# lab6.net
KiCad netlist of a schematic drawn in EAGLE
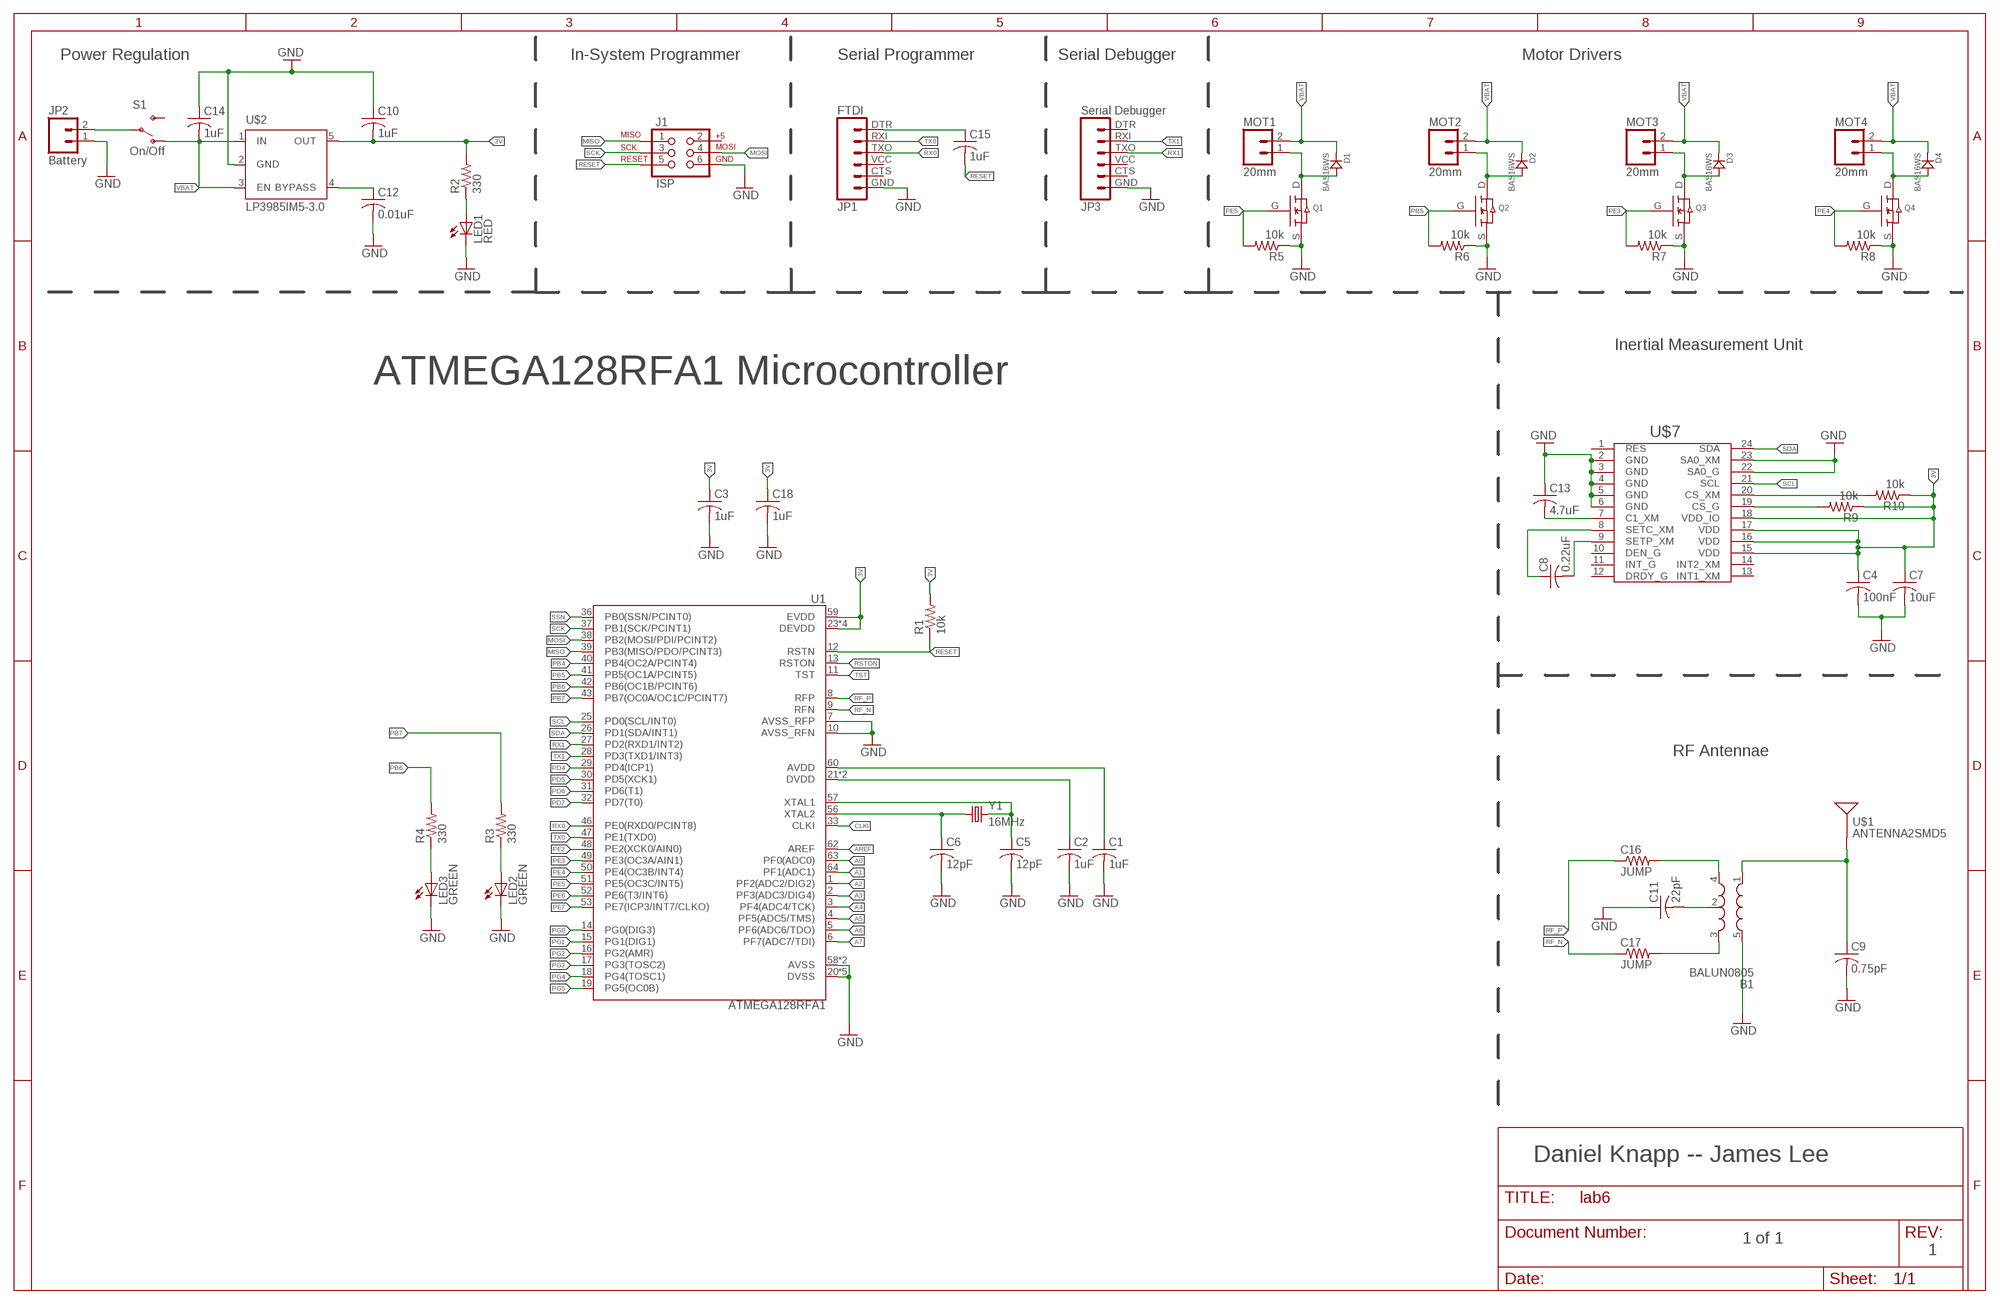
[diagram p0: schematic, sheet 1]

(export (version "E")
  (design (tool "Eeschema 10.0.6"))
  (components
    (comp (ref "B1")
      (value "BALUN0805")
      (footprint "eagle-import:BALUN")
      (libsource (lib "eagle-import") (part "BALUN0805"))
    )
    (comp (ref "C1")
      (value "1uF")
      (footprint "eagle-import:C0805")
      (libsource (lib "eagle-import") (part "C-USC0805"))
    )
    (comp (ref "C2")
      (value "1uF")
      (footprint "eagle-import:C0805")
      (libsource (lib "eagle-import") (part "C-USC0805"))
    )
    (comp (ref "C3")
      (value "1uF")
      (footprint "eagle-import:C0805")
      (libsource (lib "eagle-import") (part "C-USC0805"))
    )
    (comp (ref "C4")
      (value "100nF")
      (footprint "eagle-import:C0805")
      (libsource (lib "eagle-import") (part "C-USC0805"))
    )
    (comp (ref "C5")
      (value "12pF")
      (footprint "eagle-import:C0805")
      (libsource (lib "eagle-import") (part "C-USC0805"))
    )
    (comp (ref "C6")
      (value "12pF")
      (footprint "eagle-import:C0805")
      (libsource (lib "eagle-import") (part "C-USC0805"))
    )
    (comp (ref "C7")
      (value "10uF")
      (footprint "eagle-import:C0805")
      (libsource (lib "eagle-import") (part "C-USC0805"))
    )
    (comp (ref "C8")
      (value "0.22uF")
      (footprint "eagle-import:C0805")
      (libsource (lib "eagle-import") (part "C-USC0805"))
    )
    (comp (ref "C9")
      (value "0.75pF")
      (footprint "eagle-import:C0805")
      (libsource (lib "eagle-import") (part "C-USC0805"))
    )
    (comp (ref "C10")
      (value "1uF")
      (footprint "eagle-import:C0805")
      (libsource (lib "eagle-import") (part "C-USC0805"))
    )
    (comp (ref "C11")
      (value "22pF")
      (footprint "eagle-import:C0805")
      (libsource (lib "eagle-import") (part "C-USC0805"))
    )
    (comp (ref "C12")
      (value "0.01uF")
      (footprint "eagle-import:C0805")
      (libsource (lib "eagle-import") (part "C-USC0805"))
    )
    (comp (ref "C13")
      (value "4.7uF")
      (footprint "eagle-import:C0805")
      (libsource (lib "eagle-import") (part "C-USC0805"))
    )
    (comp (ref "C14")
      (value "1uF")
      (footprint "eagle-import:C0805")
      (libsource (lib "eagle-import") (part "C-USC0805"))
    )
    (comp (ref "C15")
      (value "1uF")
      (footprint "eagle-import:C0805")
      (libsource (lib "eagle-import") (part "C-USC0805"))
    )
    (comp (ref "C16")
      (value "JUMP")
      (footprint "eagle-import:R0805")
      (libsource (lib "eagle-import") (part "R-US_R0805"))
    )
    (comp (ref "C17")
      (value "JUMP")
      (footprint "eagle-import:R0805")
      (libsource (lib "eagle-import") (part "R-US_R0805"))
    )
    (comp (ref "C18")
      (value "1uF")
      (footprint "eagle-import:C0805")
      (libsource (lib "eagle-import") (part "C-USC0805"))
    )
    (comp (ref "D1")
      (value "BAS16WS")
      (footprint "eagle-import:BAS16WS")
      (fields (field (name "CREATOR") "Daniel Knapp"))
      (libsource (lib "eagle-import") (part "BAS16WS"))
    )
    (comp (ref "D2")
      (value "BAS16WS")
      (footprint "eagle-import:BAS16WS")
      (fields (field (name "CREATOR") "Daniel Knapp"))
      (libsource (lib "eagle-import") (part "BAS16WS"))
    )
    (comp (ref "D3")
      (value "BAS16WS")
      (footprint "eagle-import:BAS16WS")
      (fields (field (name "CREATOR") "Daniel Knapp"))
      (libsource (lib "eagle-import") (part "BAS16WS"))
    )
    (comp (ref "D4")
      (value "BAS16WS")
      (footprint "eagle-import:BAS16WS")
      (fields (field (name "CREATOR") "Daniel Knapp"))
      (libsource (lib "eagle-import") (part "BAS16WS"))
    )
    (comp (ref "J1")
      (value "ISP")
      (footprint "eagle-import:2X3-NS")
      (libsource (lib "eagle-import") (part "AVR_SPI_PRG_6NS"))
    )
    (comp (ref "JP1")
      (value "FTDI")
      (footprint "eagle-import:FTDI_BASIC")
      (libsource (lib "eagle-import") (part "FTDI_BASICPTH"))
    )
    (comp (ref "JP2")
      (value "Battery")
      (footprint "eagle-import:1X02")
      (libsource (lib "eagle-import") (part "M02PTH"))
    )
    (comp (ref "JP3")
      (value "Serial Debugger")
      (footprint "eagle-import:FTDI_BASIC")
      (libsource (lib "eagle-import") (part "FTDI_BASICPTH"))
    )
    (comp (ref "LED1")
      (value "RED")
      (footprint "eagle-import:CHIP-LED0805")
      (libsource (lib "eagle-import") (part "LEDCHIP-LED0805"))
    )
    (comp (ref "LED2")
      (value "GREEN")
      (footprint "eagle-import:CHIP-LED0805")
      (libsource (lib "eagle-import") (part "LEDCHIP-LED0805"))
    )
    (comp (ref "LED3")
      (value "GREEN")
      (footprint "eagle-import:CHIP-LED0805")
      (libsource (lib "eagle-import") (part "LEDCHIP-LED0805"))
    )
    (comp (ref "MOT1")
      (value "20mm")
      (footprint "eagle-import:1X02")
      (libsource (lib "eagle-import") (part "M02PTH"))
    )
    (comp (ref "MOT2")
      (value "20mm")
      (footprint "eagle-import:1X02")
      (libsource (lib "eagle-import") (part "M02PTH"))
    )
    (comp (ref "MOT3")
      (value "20mm")
      (footprint "eagle-import:1X02")
      (libsource (lib "eagle-import") (part "M02PTH"))
    )
    (comp (ref "MOT4")
      (value "20mm")
      (footprint "eagle-import:1X02")
      (libsource (lib "eagle-import") (part "M02PTH"))
    )
    (comp (ref "Q1")
      (value "SI2302CDS")
      (footprint "eagle-import:SI2302CDS")
      (fields (field (name "CREATOR") "Daniel Knapp"))
      (libsource (lib "eagle-import") (part "SI2302CDS"))
    )
    (comp (ref "Q2")
      (value "SI2302CDS")
      (footprint "eagle-import:SI2302CDS")
      (fields (field (name "CREATOR") "Daniel Knapp"))
      (libsource (lib "eagle-import") (part "SI2302CDS"))
    )
    (comp (ref "Q3")
      (value "SI2302CDS")
      (footprint "eagle-import:SI2302CDS")
      (fields (field (name "CREATOR") "Daniel Knapp"))
      (libsource (lib "eagle-import") (part "SI2302CDS"))
    )
    (comp (ref "Q4")
      (value "SI2302CDS")
      (footprint "eagle-import:SI2302CDS")
      (fields (field (name "CREATOR") "Daniel Knapp"))
      (libsource (lib "eagle-import") (part "SI2302CDS"))
    )
    (comp (ref "R1")
      (value "10k")
      (footprint "eagle-import:R0805")
      (libsource (lib "eagle-import") (part "R-US_R0805"))
    )
    (comp (ref "R2")
      (value "330")
      (footprint "eagle-import:R0805")
      (libsource (lib "eagle-import") (part "R-US_R0805"))
    )
    (comp (ref "R3")
      (value "330")
      (footprint "eagle-import:R0805")
      (libsource (lib "eagle-import") (part "R-US_R0805"))
    )
    (comp (ref "R4")
      (value "330")
      (footprint "eagle-import:R0805")
      (libsource (lib "eagle-import") (part "R-US_R0805"))
    )
    (comp (ref "R5")
      (value "10k")
      (footprint "eagle-import:R0805")
      (libsource (lib "eagle-import") (part "R-US_R0805"))
    )
    (comp (ref "R6")
      (value "10k")
      (footprint "eagle-import:R0805")
      (libsource (lib "eagle-import") (part "R-US_R0805"))
    )
    (comp (ref "R7")
      (value "10k")
      (footprint "eagle-import:R0805")
      (libsource (lib "eagle-import") (part "R-US_R0805"))
    )
    (comp (ref "R8")
      (value "10k")
      (footprint "eagle-import:R0805")
      (libsource (lib "eagle-import") (part "R-US_R0805"))
    )
    (comp (ref "R9")
      (value "10k")
      (footprint "eagle-import:R0805")
      (libsource (lib "eagle-import") (part "R-US_R0805"))
    )
    (comp (ref "R10")
      (value "10k")
      (footprint "eagle-import:R0805")
      (libsource (lib "eagle-import") (part "R-US_R0805"))
    )
    (comp (ref "S1")
      (value "On/Off")
      (footprint "eagle-import:SWITCH-SPDT")
      (libsource (lib "eagle-import") (part "SWITCH-SPDTPTH"))
    )
    (comp (ref "U$1")
      (value "ANTENNA2SMD5")
      (footprint "eagle-import:ANTENNA-CHIP5")
      (libsource (lib "eagle-import") (part "ANTENNA2SMD5"))
    )
    (comp (ref "U$2")
      (value "LP3985IM5-3.0")
      (footprint "eagle-import:SOT23-DBV")
      (libsource (lib "eagle-import") (part "LP3985IM5-3.0"))
    )
    (comp (ref "U$7")
      (value "LSM9DS0")
      (footprint "eagle-import:LSM9DS0")
      (fields (field (name "CREATOR") "Daniel Knapp"))
      (libsource (lib "eagle-import") (part "LSM9DS0"))
    )
    (comp (ref "U1")
      (value "ATMEGA128RFA1")
      (footprint "eagle-import:QFN-64")
      (libsource (lib "eagle-import") (part "ATMEGA128RFA1"))
    )
    (comp (ref "Y1")
      (value "16MHz")
      (footprint "eagle-import:CRYSTAL-SMD-5X3")
      (libsource (lib "eagle-import") (part "CRYSTAL5X3"))
    )
  )
  (nets
    (net (code "1") (name "3V") (class "Default")
      (node (ref "C10") (pin "2") (pinfunction "2_2") (pintype "passive"))
      (node (ref "C18") (pin "1") (pinfunction "1_1") (pintype "passive"))
      (node (ref "C3") (pin "1") (pinfunction "1_1") (pintype "passive"))
      (node (ref "C4") (pin "1") (pinfunction "1_1") (pintype "passive"))
      (node (ref "C7") (pin "1") (pinfunction "1_1") (pintype "passive"))
      (node (ref "R1") (pin "2") (pinfunction "2_2") (pintype "passive"))
      (node (ref "R10") (pin "1") (pinfunction "1_1") (pintype "passive"))
      (node (ref "R2") (pin "2") (pinfunction "2_2") (pintype "passive"))
      (node (ref "R9") (pin "1") (pinfunction "1_1") (pintype "passive"))
      (node (ref "U$2") (pin "5") (pinfunction "OUT_5") (pintype "passive"))
      (node (ref "U$7") (pin "15") (pinfunction "VDD_15") (pintype "bidirectional"))
      (node (ref "U$7") (pin "16") (pinfunction "VDD_16") (pintype "bidirectional"))
      (node (ref "U$7") (pin "17") (pinfunction "VDD_17") (pintype "bidirectional"))
      (node (ref "U$7") (pin "18") (pinfunction "VDD_IO_18") (pintype "bidirectional"))
      (node (ref "U1") (pin "23") (pinfunction "DEVDD_23") (pintype "bidirectional"))
      (node (ref "U1") (pin "34") (pinfunction "DEVDD_34") (pintype "bidirectional"))
      (node (ref "U1") (pin "44") (pinfunction "DEVDD_44") (pintype "bidirectional"))
      (node (ref "U1") (pin "54") (pinfunction "DEVDD_54") (pintype "bidirectional"))
      (node (ref "U1") (pin "59") (pinfunction "EVDD_59") (pintype "bidirectional"))
    )
    (net (code "2") (name "A0") (class "Default")
      (node (ref "U1") (pin "63") (pinfunction "PF0(ADC0)_63") (pintype "bidirectional"))
    )
    (net (code "3") (name "A1") (class "Default")
      (node (ref "U1") (pin "64") (pinfunction "PF1(ADC1)_64") (pintype "bidirectional"))
    )
    (net (code "4") (name "A2") (class "Default")
      (node (ref "U1") (pin "1") (pinfunction "PF2(ADC2/DIG2)_1") (pintype "bidirectional"))
    )
    (net (code "5") (name "A3") (class "Default")
      (node (ref "U1") (pin "2") (pinfunction "PF3(ADC3/DIG4)_2") (pintype "bidirectional"))
    )
    (net (code "6") (name "A4") (class "Default")
      (node (ref "U1") (pin "3") (pinfunction "PF4(ADC4/TCK)_3") (pintype "bidirectional"))
    )
    (net (code "7") (name "A5") (class "Default")
      (node (ref "U1") (pin "4") (pinfunction "PF5(ADC5/TMS)_4") (pintype "bidirectional"))
    )
    (net (code "8") (name "A6") (class "Default")
      (node (ref "U1") (pin "5") (pinfunction "PF6(ADC6/TDO)_5") (pintype "bidirectional"))
    )
    (net (code "9") (name "A7") (class "Default")
      (node (ref "U1") (pin "6") (pinfunction "PF7(ADC7/TDI)_6") (pintype "bidirectional"))
    )
    (net (code "10") (name "AREF") (class "Default")
      (node (ref "U1") (pin "62") (pinfunction "AREF_62") (pintype "bidirectional"))
    )
    (net (code "11") (name "CLKI") (class "Default")
      (node (ref "U1") (pin "33") (pinfunction "CLKI_33") (pintype "bidirectional"))
    )
    (net (code "12") (name "GND") (class "Default")
      (node (ref "B1") (pin "5") (pinfunction "GND_5") (pintype "bidirectional"))
      (node (ref "C1") (pin "2") (pinfunction "2_2") (pintype "passive"))
      (node (ref "C10") (pin "1") (pinfunction "1_1") (pintype "passive"))
      (node (ref "C11") (pin "1") (pinfunction "1_1") (pintype "passive"))
      (node (ref "C12") (pin "2") (pinfunction "2_2") (pintype "passive"))
      (node (ref "C13") (pin "1") (pinfunction "1_1") (pintype "passive"))
      (node (ref "C14") (pin "1") (pinfunction "1_1") (pintype "passive"))
      (node (ref "C18") (pin "2") (pinfunction "2_2") (pintype "passive"))
      (node (ref "C2") (pin "2") (pinfunction "2_2") (pintype "passive"))
      (node (ref "C3") (pin "2") (pinfunction "2_2") (pintype "passive"))
      (node (ref "C4") (pin "2") (pinfunction "2_2") (pintype "passive"))
      (node (ref "C5") (pin "2") (pinfunction "2_2") (pintype "passive"))
      (node (ref "C6") (pin "2") (pinfunction "2_2") (pintype "passive"))
      (node (ref "C7") (pin "2") (pinfunction "2_2") (pintype "passive"))
      (node (ref "C9") (pin "2") (pinfunction "2_2") (pintype "passive"))
      (node (ref "J1") (pin "6") (pinfunction "6_6") (pintype "passive"))
      (node (ref "JP1") (pin "GND") (pinfunction "6_GND") (pintype "passive"))
      (node (ref "JP2") (pin "1") (pinfunction "1_1") (pintype "passive"))
      (node (ref "JP3") (pin "GND") (pinfunction "6_GND") (pintype "passive"))
      (node (ref "LED1") (pin "C") (pinfunction "C_C") (pintype "passive"))
      (node (ref "LED2") (pin "C") (pinfunction "C_C") (pintype "passive"))
      (node (ref "LED3") (pin "C") (pinfunction "C_C") (pintype "passive"))
      (node (ref "Q1") (pin "S") (pinfunction "P$2_S") (pintype "passive"))
      (node (ref "Q2") (pin "S") (pinfunction "P$2_S") (pintype "passive"))
      (node (ref "Q3") (pin "S") (pinfunction "P$2_S") (pintype "passive"))
      (node (ref "Q4") (pin "S") (pinfunction "P$2_S") (pintype "passive"))
      (node (ref "R5") (pin "1") (pinfunction "1_1") (pintype "passive"))
      (node (ref "R6") (pin "1") (pinfunction "1_1") (pintype "passive"))
      (node (ref "R7") (pin "1") (pinfunction "1_1") (pintype "passive"))
      (node (ref "R8") (pin "1") (pinfunction "1_1") (pintype "passive"))
      (node (ref "U$2") (pin "2") (pinfunction "GND_2") (pintype "input"))
      (node (ref "U$7") (pin "2") (pinfunction "GND_2") (pintype "bidirectional"))
      (node (ref "U$7") (pin "22") (pinfunction "SA0_G_22") (pintype "bidirectional"))
      (node (ref "U$7") (pin "23") (pinfunction "SA0_XM_23") (pintype "bidirectional"))
      (node (ref "U$7") (pin "3") (pinfunction "GND_3") (pintype "bidirectional"))
      (node (ref "U$7") (pin "4") (pinfunction "GND_4") (pintype "bidirectional"))
      (node (ref "U$7") (pin "5") (pinfunction "GND_5") (pintype "bidirectional"))
      (node (ref "U$7") (pin "6") (pinfunction "GND_6") (pintype "bidirectional"))
      (node (ref "U1") (pin "10") (pinfunction "AVSS_RFN_10") (pintype "bidirectional"))
      (node (ref "U1") (pin "20") (pinfunction "DVSS_20") (pintype "bidirectional"))
      (node (ref "U1") (pin "24") (pinfunction "DVSS_24") (pintype "bidirectional"))
      (node (ref "U1") (pin "35") (pinfunction "DVSS_35") (pintype "bidirectional"))
      (node (ref "U1") (pin "45") (pinfunction "DVSS_45") (pintype "bidirectional"))
      (node (ref "U1") (pin "55") (pinfunction "DVSS_55") (pintype "bidirectional"))
      (node (ref "U1") (pin "58") (pinfunction "AVSS_58") (pintype "bidirectional"))
      (node (ref "U1") (pin "61") (pinfunction "AVSS_61") (pintype "bidirectional"))
      (node (ref "U1") (pin "7") (pinfunction "AVSS_RFP_7") (pintype "bidirectional"))
    )
    (net (code "13") (name "MISO") (class "Default")
      (node (ref "J1") (pin "1") (pinfunction "1_1") (pintype "passive"))
      (node (ref "U1") (pin "39") (pinfunction "PB3(MISO/PDO/PCINT3)_39") (pintype "bidirectional"))
    )
    (net (code "14") (name "MOSI") (class "Default")
      (node (ref "J1") (pin "4") (pinfunction "4_4") (pintype "passive"))
      (node (ref "U1") (pin "38") (pinfunction "PB2(MOSI/PDI/PCINT2)_38") (pintype "bidirectional"))
    )
    (net (code "15") (name "Net-(B1-GND-Pad2)") (class "Default")
      (node (ref "B1") (pin "2") (pinfunction "GND_2") (pintype "bidirectional"))
      (node (ref "C11") (pin "2") (pinfunction "2_2") (pintype "passive"))
    )
    (net (code "16") (name "Net-(B1-IN)") (class "Default")
      (node (ref "B1") (pin "1") (pinfunction "IN_1") (pintype "bidirectional"))
      (node (ref "C9") (pin "1") (pinfunction "1_1") (pintype "passive"))
      (node (ref "U$1") (pin "FEED") (pinfunction "SIGNAL_FEED") (pintype "bidirectional"))
    )
    (net (code "17") (name "Net-(B1-OUT1)") (class "Default")
      (node (ref "B1") (pin "4") (pinfunction "OUT1_4") (pintype "bidirectional"))
      (node (ref "C16") (pin "2") (pinfunction "2_2") (pintype "passive"))
    )
    (net (code "18") (name "Net-(B1-OUT2)") (class "Default")
      (node (ref "B1") (pin "3") (pinfunction "OUT2_3") (pintype "bidirectional"))
      (node (ref "C17") (pin "2") (pinfunction "2_2") (pintype "passive"))
    )
    (net (code "19") (name "Net-(C2-Pad1)") (class "Default")
      (node (ref "C2") (pin "1") (pinfunction "1_1") (pintype "passive"))
      (node (ref "U1") (pin "21") (pinfunction "DVDD_21") (pintype "bidirectional"))
      (node (ref "U1") (pin "22") (pinfunction "DVDD_22") (pintype "bidirectional"))
    )
    (net (code "20") (name "Net-(JP1-1)") (class "Default")
      (node (ref "C15") (pin "1") (pinfunction "1_1") (pintype "passive"))
      (node (ref "JP1") (pin "DTR") (pinfunction "1_DTR") (pintype "passive"))
    )
    (net (code "21") (name "Net-(LED1-PadA)") (class "Default")
      (node (ref "LED1") (pin "A") (pinfunction "A_A") (pintype "passive"))
      (node (ref "R2") (pin "1") (pinfunction "1_1") (pintype "passive"))
    )
    (net (code "22") (name "Net-(LED2-PadA)") (class "Default")
      (node (ref "LED2") (pin "A") (pinfunction "A_A") (pintype "passive"))
      (node (ref "R3") (pin "1") (pinfunction "1_1") (pintype "passive"))
    )
    (net (code "23") (name "Net-(LED3-PadA)") (class "Default")
      (node (ref "LED3") (pin "A") (pinfunction "A_A") (pintype "passive"))
      (node (ref "R4") (pin "1") (pinfunction "1_1") (pintype "passive"))
    )
    (net (code "24") (name "Net-(Q1-P$3)") (class "Default")
      (node (ref "D1") (pin "P$2") (pinfunction "P$2_P$2") (pintype "passive"))
      (node (ref "MOT1") (pin "1") (pinfunction "1_1") (pintype "passive"))
      (node (ref "Q1") (pin "D") (pinfunction "P$3_D") (pintype "passive"))
    )
    (net (code "25") (name "Net-(Q2-P$3)") (class "Default")
      (node (ref "D2") (pin "P$2") (pinfunction "P$2_P$2") (pintype "passive"))
      (node (ref "MOT2") (pin "1") (pinfunction "1_1") (pintype "passive"))
      (node (ref "Q2") (pin "D") (pinfunction "P$3_D") (pintype "passive"))
    )
    (net (code "26") (name "Net-(Q3-P$3)") (class "Default")
      (node (ref "D3") (pin "P$2") (pinfunction "P$2_P$2") (pintype "passive"))
      (node (ref "MOT3") (pin "1") (pinfunction "1_1") (pintype "passive"))
      (node (ref "Q3") (pin "D") (pinfunction "P$3_D") (pintype "passive"))
    )
    (net (code "27") (name "Net-(Q4-P$3)") (class "Default")
      (node (ref "D4") (pin "P$2") (pinfunction "P$2_P$2") (pintype "passive"))
      (node (ref "MOT4") (pin "1") (pinfunction "1_1") (pintype "passive"))
      (node (ref "Q4") (pin "D") (pinfunction "P$3_D") (pintype "passive"))
    )
    (net (code "28") (name "Net-(S1-P)") (class "Default")
      (node (ref "JP2") (pin "2") (pinfunction "2_2") (pintype "passive"))
      (node (ref "S1") (pin "2") (pinfunction "P_2") (pintype "passive"))
    )
    (net (code "29") (name "Net-(U$2-BYPASS)") (class "Default")
      (node (ref "C12") (pin "1") (pinfunction "1_1") (pintype "passive"))
      (node (ref "U$2") (pin "4") (pinfunction "BYPASS_4") (pintype "passive"))
    )
    (net (code "30") (name "Net-(U$7-C1_XM)") (class "Default")
      (node (ref "C13") (pin "2") (pinfunction "2_2") (pintype "passive"))
      (node (ref "U$7") (pin "7") (pinfunction "C1_XM_7") (pintype "bidirectional"))
    )
    (net (code "31") (name "Net-(U$7-CS_G)") (class "Default")
      (node (ref "R9") (pin "2") (pinfunction "2_2") (pintype "passive"))
      (node (ref "U$7") (pin "19") (pinfunction "CS_G_19") (pintype "bidirectional"))
    )
    (net (code "32") (name "Net-(U$7-CS_XM)") (class "Default")
      (node (ref "R10") (pin "2") (pinfunction "2_2") (pintype "passive"))
      (node (ref "U$7") (pin "20") (pinfunction "CS_XM_20") (pintype "bidirectional"))
    )
    (net (code "33") (name "Net-(U$7-SETC_XM)") (class "Default")
      (node (ref "C8") (pin "1") (pinfunction "1_1") (pintype "passive"))
      (node (ref "U$7") (pin "8") (pinfunction "SETC_XM_8") (pintype "bidirectional"))
    )
    (net (code "34") (name "Net-(U$7-SETP_XM)") (class "Default")
      (node (ref "C8") (pin "2") (pinfunction "2_2") (pintype "passive"))
      (node (ref "U$7") (pin "9") (pinfunction "SETP_XM_9") (pintype "bidirectional"))
    )
    (net (code "35") (name "Net-(U1-AVDD)") (class "Default")
      (node (ref "C1") (pin "1") (pinfunction "1_1") (pintype "passive"))
      (node (ref "U1") (pin "60") (pinfunction "AVDD_60") (pintype "bidirectional"))
    )
    (net (code "36") (name "Net-(U1-XTAL1)") (class "Default")
      (node (ref "C5") (pin "1") (pinfunction "1_1") (pintype "passive"))
      (node (ref "U1") (pin "57") (pinfunction "XTAL1_57") (pintype "bidirectional"))
      (node (ref "Y1") (pin "3") (pinfunction "2_3") (pintype "passive"))
    )
    (net (code "37") (name "Net-(U1-XTAL2)") (class "Default")
      (node (ref "C6") (pin "1") (pinfunction "1_1") (pintype "passive"))
      (node (ref "U1") (pin "56") (pinfunction "XTAL2_56") (pintype "bidirectional"))
      (node (ref "Y1") (pin "1") (pinfunction "1_1") (pintype "passive"))
    )
    (net (code "38") (name "PB4") (class "Default")
      (node (ref "U1") (pin "40") (pinfunction "PB4(OC2A/PCINT4)_40") (pintype "bidirectional"))
    )
    (net (code "39") (name "PB5") (class "Default")
      (node (ref "Q2") (pin "G") (pinfunction "P$1_G") (pintype "passive"))
      (node (ref "R6") (pin "2") (pinfunction "2_2") (pintype "passive"))
      (node (ref "U1") (pin "41") (pinfunction "PB5(OC1A/PCINT5)_41") (pintype "bidirectional"))
    )
    (net (code "40") (name "PB6") (class "Default")
      (node (ref "R4") (pin "2") (pinfunction "2_2") (pintype "passive"))
      (node (ref "U1") (pin "42") (pinfunction "PB6(OC1B/PCINT6)_42") (pintype "bidirectional"))
    )
    (net (code "41") (name "PB7") (class "Default")
      (node (ref "R3") (pin "2") (pinfunction "2_2") (pintype "passive"))
      (node (ref "U1") (pin "43") (pinfunction "PB7(OC0A/OC1C/PCINT7)_43") (pintype "bidirectional"))
    )
    (net (code "42") (name "PD4") (class "Default")
      (node (ref "U1") (pin "29") (pinfunction "PD4(ICP1)_29") (pintype "bidirectional"))
    )
    (net (code "43") (name "PD5") (class "Default")
      (node (ref "U1") (pin "30") (pinfunction "PD5(XCK1)_30") (pintype "bidirectional"))
    )
    (net (code "44") (name "PD6") (class "Default")
      (node (ref "U1") (pin "31") (pinfunction "PD6(T1)_31") (pintype "bidirectional"))
    )
    (net (code "45") (name "PD7") (class "Default")
      (node (ref "U1") (pin "32") (pinfunction "PD7(T0)_32") (pintype "bidirectional"))
    )
    (net (code "46") (name "PE2") (class "Default")
      (node (ref "U1") (pin "48") (pinfunction "PE2(XCK0/AIN0)_48") (pintype "bidirectional"))
    )
    (net (code "47") (name "PE3") (class "Default")
      (node (ref "Q3") (pin "G") (pinfunction "P$1_G") (pintype "passive"))
      (node (ref "R7") (pin "2") (pinfunction "2_2") (pintype "passive"))
      (node (ref "U1") (pin "49") (pinfunction "PE3(OC3A/AIN1)_49") (pintype "bidirectional"))
    )
    (net (code "48") (name "PE4") (class "Default")
      (node (ref "Q4") (pin "G") (pinfunction "P$1_G") (pintype "passive"))
      (node (ref "R8") (pin "2") (pinfunction "2_2") (pintype "passive"))
      (node (ref "U1") (pin "50") (pinfunction "PE4(OC3B/INT4)_50") (pintype "bidirectional"))
    )
    (net (code "49") (name "PE5") (class "Default")
      (node (ref "Q1") (pin "G") (pinfunction "P$1_G") (pintype "passive"))
      (node (ref "R5") (pin "2") (pinfunction "2_2") (pintype "passive"))
      (node (ref "U1") (pin "51") (pinfunction "PE5(OC3C/INT5)_51") (pintype "bidirectional"))
    )
    (net (code "50") (name "PE6") (class "Default")
      (node (ref "U1") (pin "52") (pinfunction "PE6(T3/INT6)_52") (pintype "bidirectional"))
    )
    (net (code "51") (name "PE7") (class "Default")
      (node (ref "U1") (pin "53") (pinfunction "PE7(ICP3/INT7/CLKO)_53") (pintype "bidirectional"))
    )
    (net (code "52") (name "PG0") (class "Default")
      (node (ref "U1") (pin "14") (pinfunction "PG0(DIG3)_14") (pintype "bidirectional"))
    )
    (net (code "53") (name "PG1") (class "Default")
      (node (ref "U1") (pin "15") (pinfunction "PG1(DIG1)_15") (pintype "bidirectional"))
    )
    (net (code "54") (name "PG2") (class "Default")
      (node (ref "U1") (pin "16") (pinfunction "PG2(AMR)_16") (pintype "bidirectional"))
    )
    (net (code "55") (name "PG3") (class "Default")
      (node (ref "U1") (pin "17") (pinfunction "PG3(TOSC2)_17") (pintype "bidirectional"))
    )
    (net (code "56") (name "PG4") (class "Default")
      (node (ref "U1") (pin "18") (pinfunction "PG4(TOSC1)_18") (pintype "bidirectional"))
    )
    (net (code "57") (name "PG5") (class "Default")
      (node (ref "U1") (pin "19") (pinfunction "PG5(OC0B)_19") (pintype "bidirectional"))
    )
    (net (code "58") (name "RESET") (class "Default")
      (node (ref "C15") (pin "2") (pinfunction "2_2") (pintype "passive"))
      (node (ref "J1") (pin "5") (pinfunction "5_5") (pintype "passive"))
      (node (ref "R1") (pin "1") (pinfunction "1_1") (pintype "passive"))
      (node (ref "U1") (pin "12") (pinfunction "RSTN_12") (pintype "bidirectional"))
    )
    (net (code "59") (name "RF_N") (class "Default")
      (node (ref "C17") (pin "1") (pinfunction "1_1") (pintype "passive"))
      (node (ref "U1") (pin "9") (pinfunction "RFN_9") (pintype "bidirectional"))
    )
    (net (code "60") (name "RF_P") (class "Default")
      (node (ref "C16") (pin "1") (pinfunction "1_1") (pintype "passive"))
      (node (ref "U1") (pin "8") (pinfunction "RFP_8") (pintype "bidirectional"))
    )
    (net (code "61") (name "RSTON") (class "Default")
      (node (ref "U1") (pin "13") (pinfunction "RSTON_13") (pintype "bidirectional"))
    )
    (net (code "62") (name "RX0") (class "Default")
      (node (ref "JP1") (pin "TXO") (pinfunction "3_TXO") (pintype "passive"))
      (node (ref "U1") (pin "46") (pinfunction "PE0(RXD0/PCINT8)_46") (pintype "bidirectional"))
    )
    (net (code "63") (name "RX1") (class "Default")
      (node (ref "JP3") (pin "TXO") (pinfunction "3_TXO") (pintype "passive"))
      (node (ref "U1") (pin "27") (pinfunction "PD2(RXD1/INT2)_27") (pintype "bidirectional"))
    )
    (net (code "64") (name "SCK") (class "Default")
      (node (ref "J1") (pin "3") (pinfunction "3_3") (pintype "passive"))
      (node (ref "U1") (pin "37") (pinfunction "PB1(SCK/PCINT1)_37") (pintype "bidirectional"))
    )
    (net (code "65") (name "SCL") (class "Default")
      (node (ref "U$7") (pin "21") (pinfunction "SCL_21") (pintype "bidirectional"))
      (node (ref "U1") (pin "25") (pinfunction "PD0(SCL/INT0)_25") (pintype "bidirectional"))
    )
    (net (code "66") (name "SDA") (class "Default")
      (node (ref "U$7") (pin "24") (pinfunction "SDA_24") (pintype "bidirectional"))
      (node (ref "U1") (pin "26") (pinfunction "PD1(SDA/INT1)_26") (pintype "bidirectional"))
    )
    (net (code "67") (name "SSN") (class "Default")
      (node (ref "U1") (pin "36") (pinfunction "PB0(SSN/PCINT0)_36") (pintype "bidirectional"))
    )
    (net (code "68") (name "TST") (class "Default")
      (node (ref "U1") (pin "11") (pinfunction "TST_11") (pintype "bidirectional"))
    )
    (net (code "69") (name "TX0") (class "Default")
      (node (ref "JP1") (pin "RXI") (pinfunction "2_RXI") (pintype "passive"))
      (node (ref "U1") (pin "47") (pinfunction "PE1(TXD0)_47") (pintype "bidirectional"))
    )
    (net (code "70") (name "TX1") (class "Default")
      (node (ref "JP3") (pin "RXI") (pinfunction "2_RXI") (pintype "passive"))
      (node (ref "U1") (pin "28") (pinfunction "PD3(TXD1/INT3)_28") (pintype "bidirectional"))
    )
    (net (code "71") (name "VBAT") (class "Default")
      (node (ref "C14") (pin "2") (pinfunction "2_2") (pintype "passive"))
      (node (ref "D1") (pin "P$1") (pinfunction "P$1_P$1") (pintype "passive"))
      (node (ref "D2") (pin "P$1") (pinfunction "P$1_P$1") (pintype "passive"))
      (node (ref "D3") (pin "P$1") (pinfunction "P$1_P$1") (pintype "passive"))
      (node (ref "D4") (pin "P$1") (pinfunction "P$1_P$1") (pintype "passive"))
      (node (ref "MOT1") (pin "2") (pinfunction "2_2") (pintype "passive"))
      (node (ref "MOT2") (pin "2") (pinfunction "2_2") (pintype "passive"))
      (node (ref "MOT3") (pin "2") (pinfunction "2_2") (pintype "passive"))
      (node (ref "MOT4") (pin "2") (pinfunction "2_2") (pintype "passive"))
      (node (ref "S1") (pin "1") (pinfunction "O_1") (pintype "passive"))
      (node (ref "U$2") (pin "1") (pinfunction "IN_1") (pintype "input"))
      (node (ref "U$2") (pin "3") (pinfunction "EN_3") (pintype "input"))
    )
    (net (code "72") (name "unconnected-(J1-Pad2)") (class "Default")
      (node (ref "J1") (pin "2") (pinfunction "2_2") (pintype "passive"))
    )
    (net (code "73") (name "unconnected-(JP1-4-PadVCC)") (class "Default")
      (node (ref "JP1") (pin "VCC") (pinfunction "4_VCC") (pintype "passive"))
    )
    (net (code "74") (name "unconnected-(JP1-5-PadCTS)") (class "Default")
      (node (ref "JP1") (pin "CTS") (pinfunction "5_CTS") (pintype "passive"))
    )
    (net (code "75") (name "unconnected-(JP3-1-PadDTR)") (class "Default")
      (node (ref "JP3") (pin "DTR") (pinfunction "1_DTR") (pintype "passive"))
    )
    (net (code "76") (name "unconnected-(JP3-4-PadVCC)") (class "Default")
      (node (ref "JP3") (pin "VCC") (pinfunction "4_VCC") (pintype "passive"))
    )
    (net (code "77") (name "unconnected-(JP3-5-PadCTS)") (class "Default")
      (node (ref "JP3") (pin "CTS") (pinfunction "5_CTS") (pintype "passive"))
    )
    (net (code "78") (name "unconnected-(S1-S-Pad3)") (class "Default")
      (node (ref "S1") (pin "3") (pinfunction "S_3") (pintype "passive"))
    )
    (net (code "79") (name "unconnected-(U$7-DEN_G-Pad10)") (class "Default")
      (node (ref "U$7") (pin "10") (pinfunction "DEN_G_10") (pintype "bidirectional"))
    )
    (net (code "80") (name "unconnected-(U$7-DRDY_G-Pad12)") (class "Default")
      (node (ref "U$7") (pin "12") (pinfunction "DRDY_G_12") (pintype "bidirectional"))
    )
    (net (code "81") (name "unconnected-(U$7-INT1_XM-Pad13)") (class "Default")
      (node (ref "U$7") (pin "13") (pinfunction "INT1_XM_13") (pintype "bidirectional"))
    )
    (net (code "82") (name "unconnected-(U$7-INT2_XM-Pad14)") (class "Default")
      (node (ref "U$7") (pin "14") (pinfunction "INT2_XM_14") (pintype "bidirectional"))
    )
    (net (code "83") (name "unconnected-(U$7-INT_G-Pad11)") (class "Default")
      (node (ref "U$7") (pin "11") (pinfunction "INT_G_11") (pintype "bidirectional"))
    )
    (net (code "84") (name "unconnected-(U$7-RES-Pad1)") (class "Default")
      (node (ref "U$7") (pin "1") (pinfunction "RES_1") (pintype "bidirectional"))
    )
  )
)
